# IRIS1304_v2_22.net
KiCad netlist of a schematic drawn in EAGLE
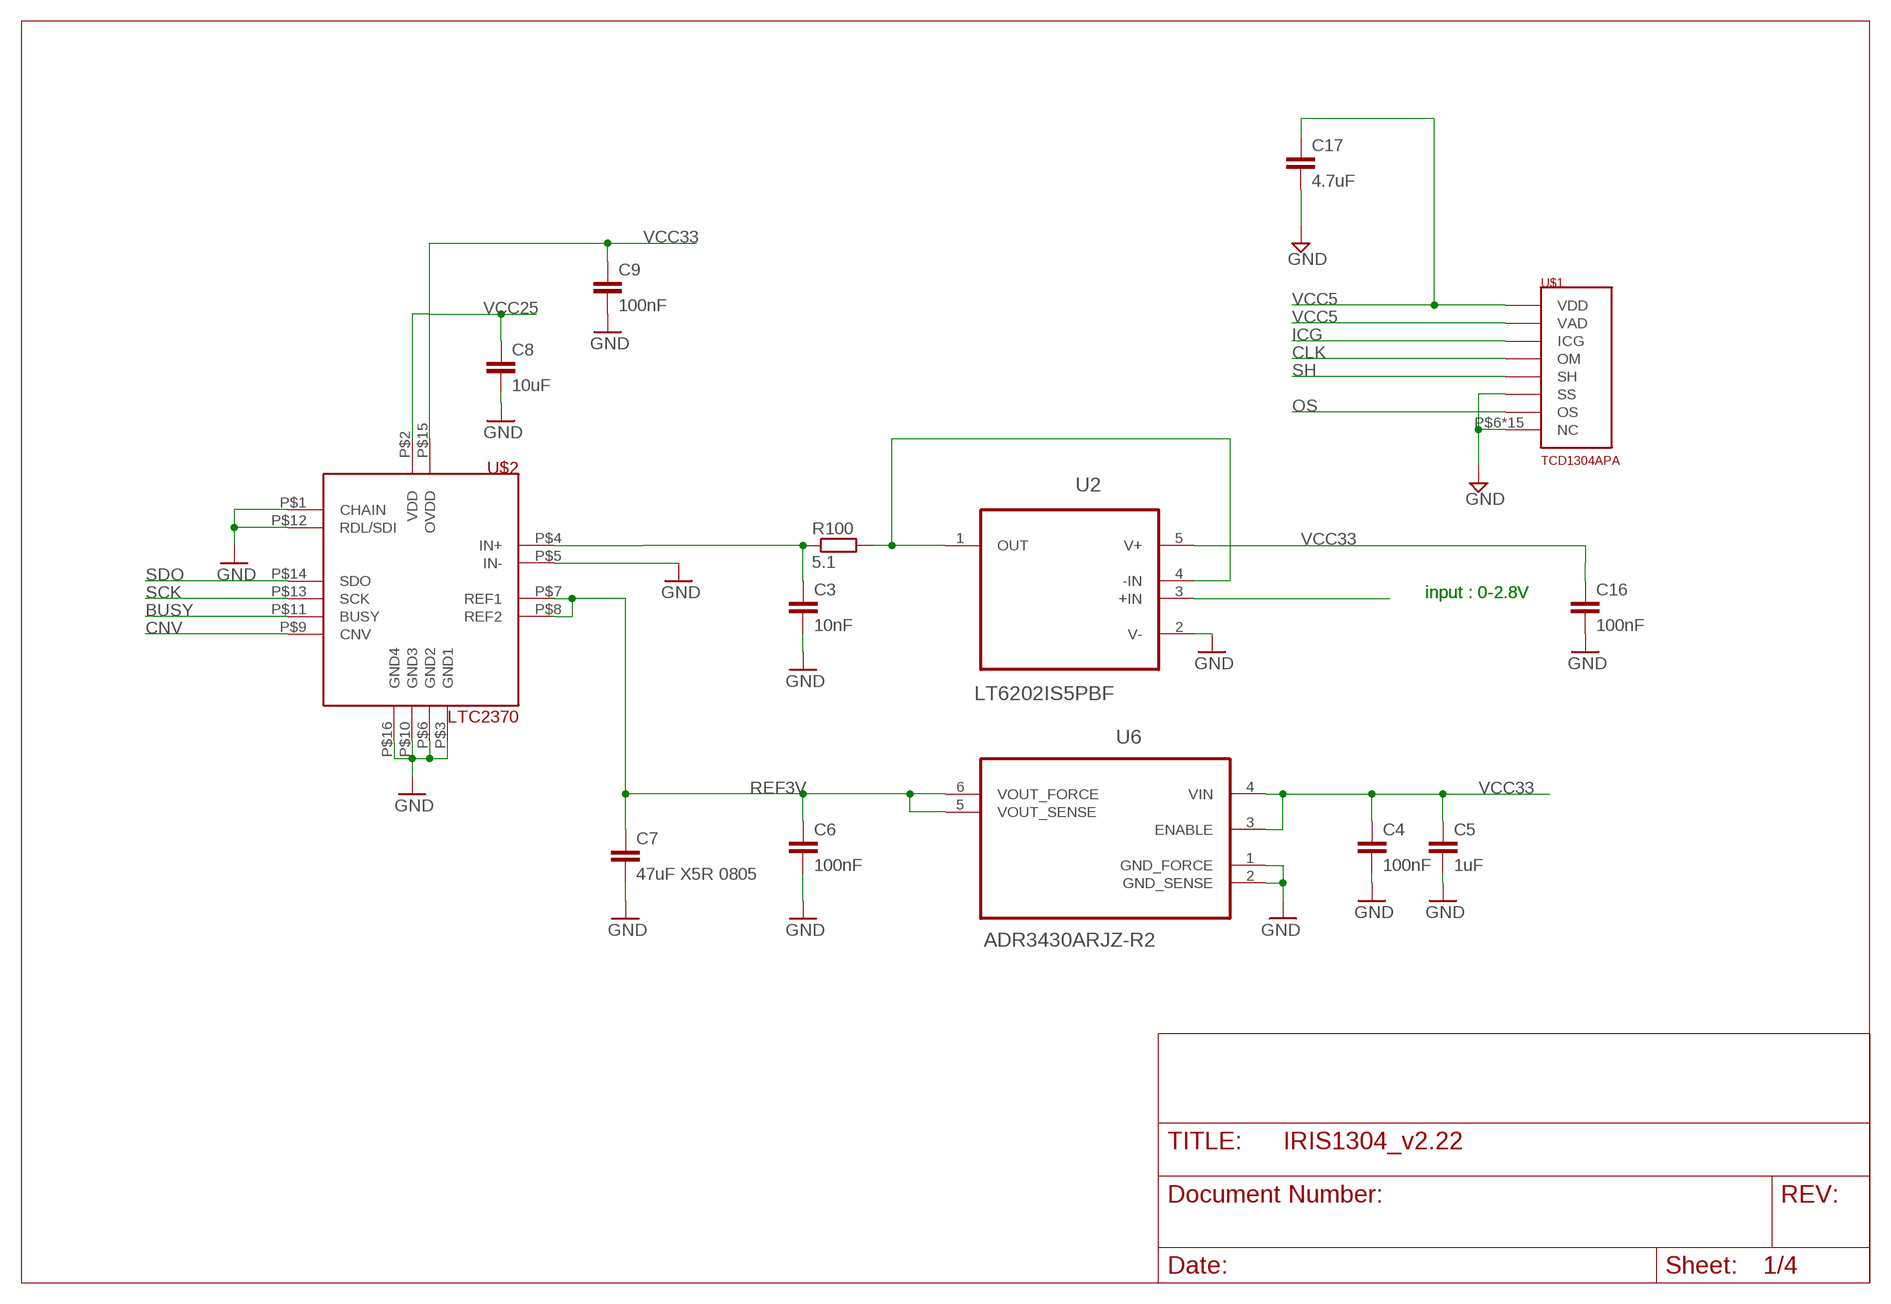
[diagram p0: schematic, sheet 1]
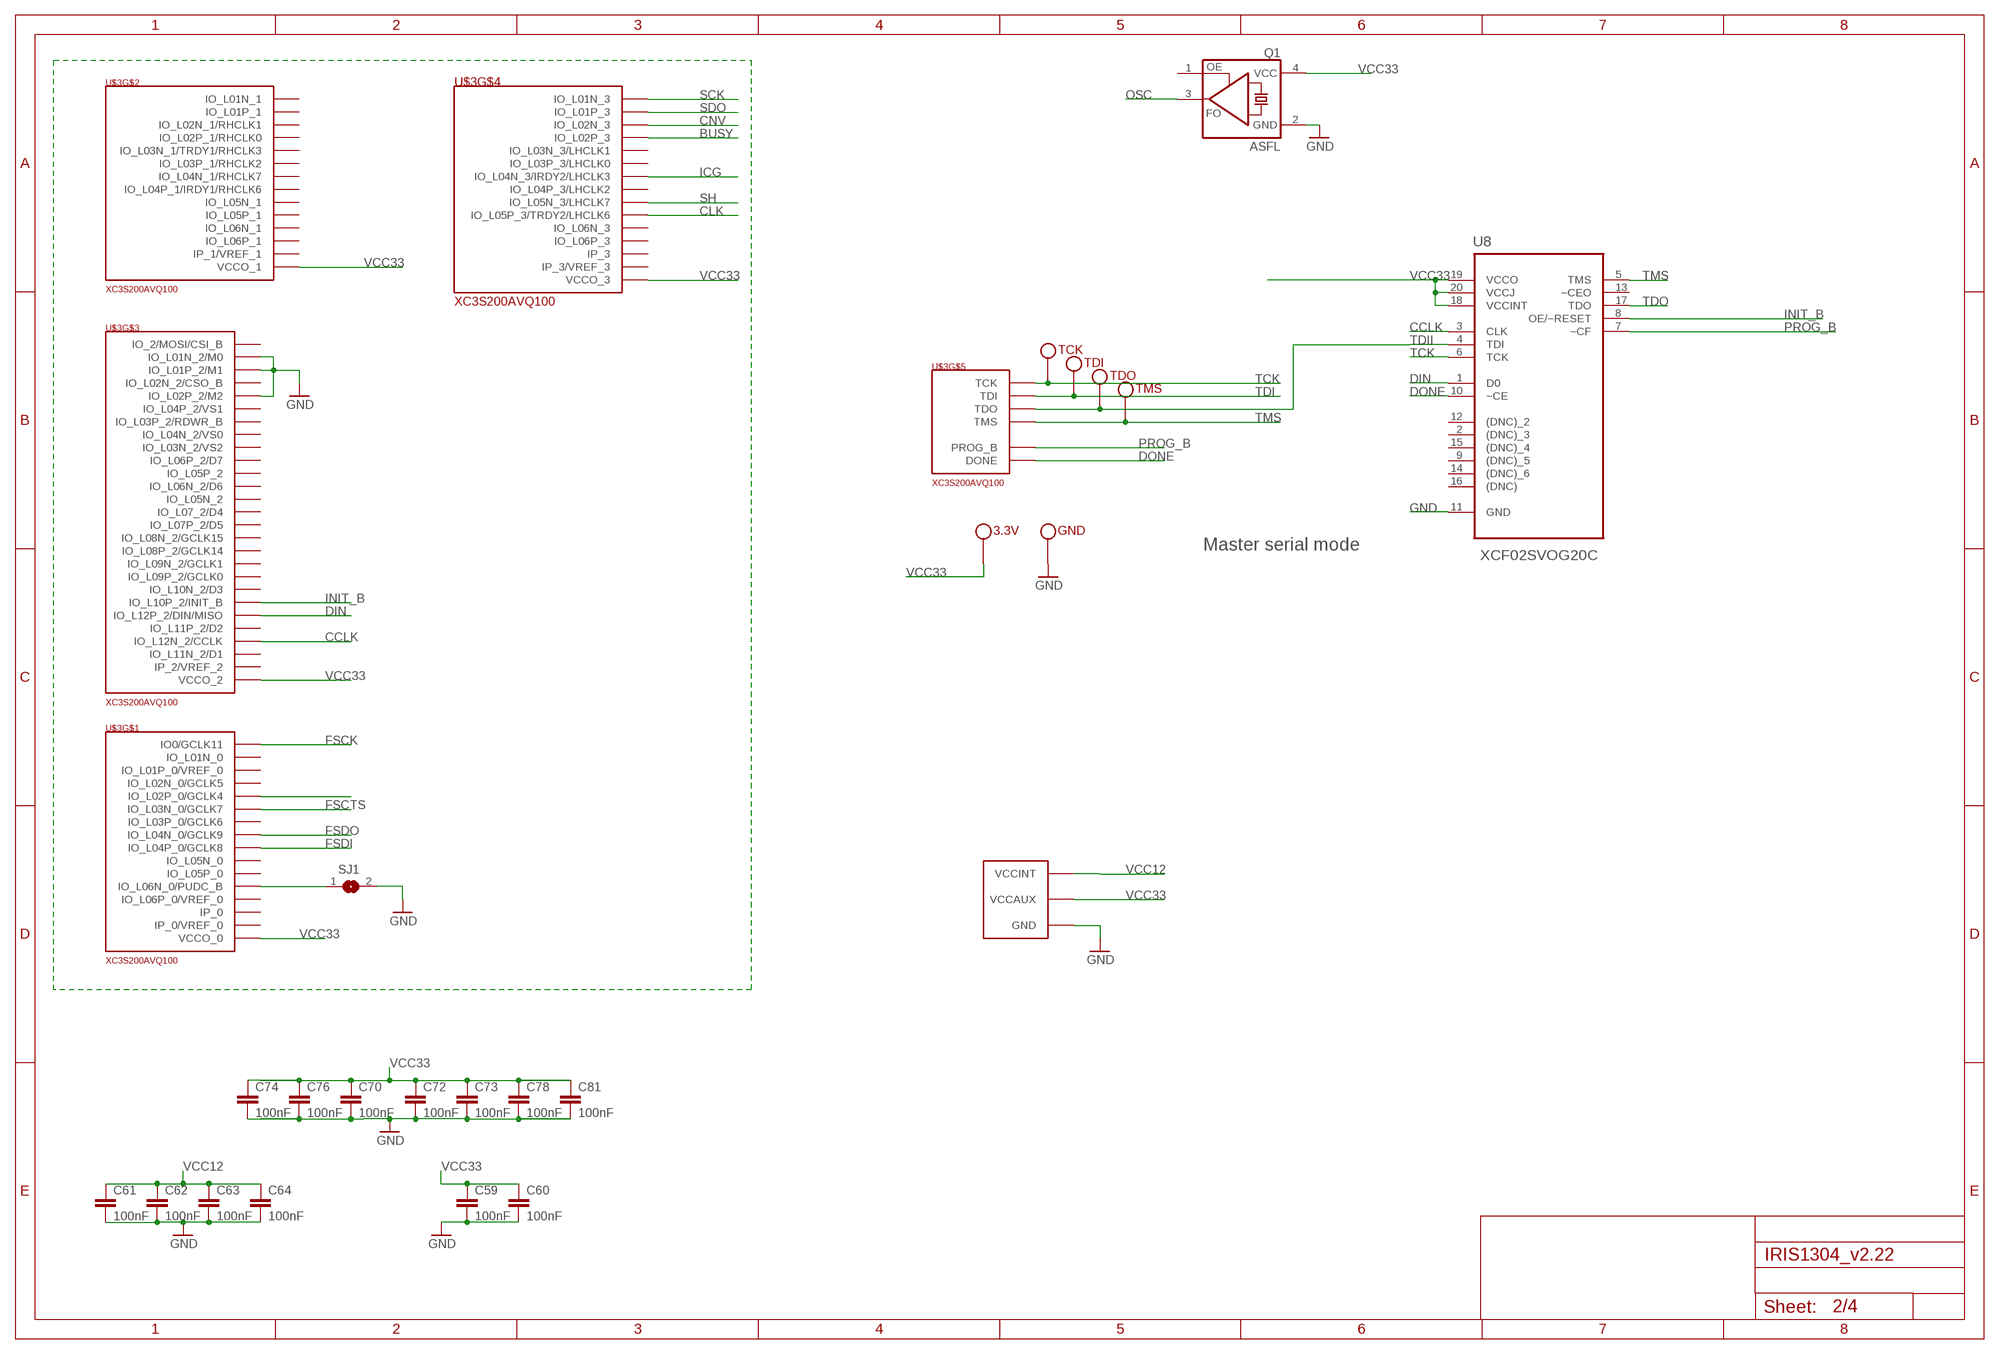
[diagram p1: schematic, sheet 2]
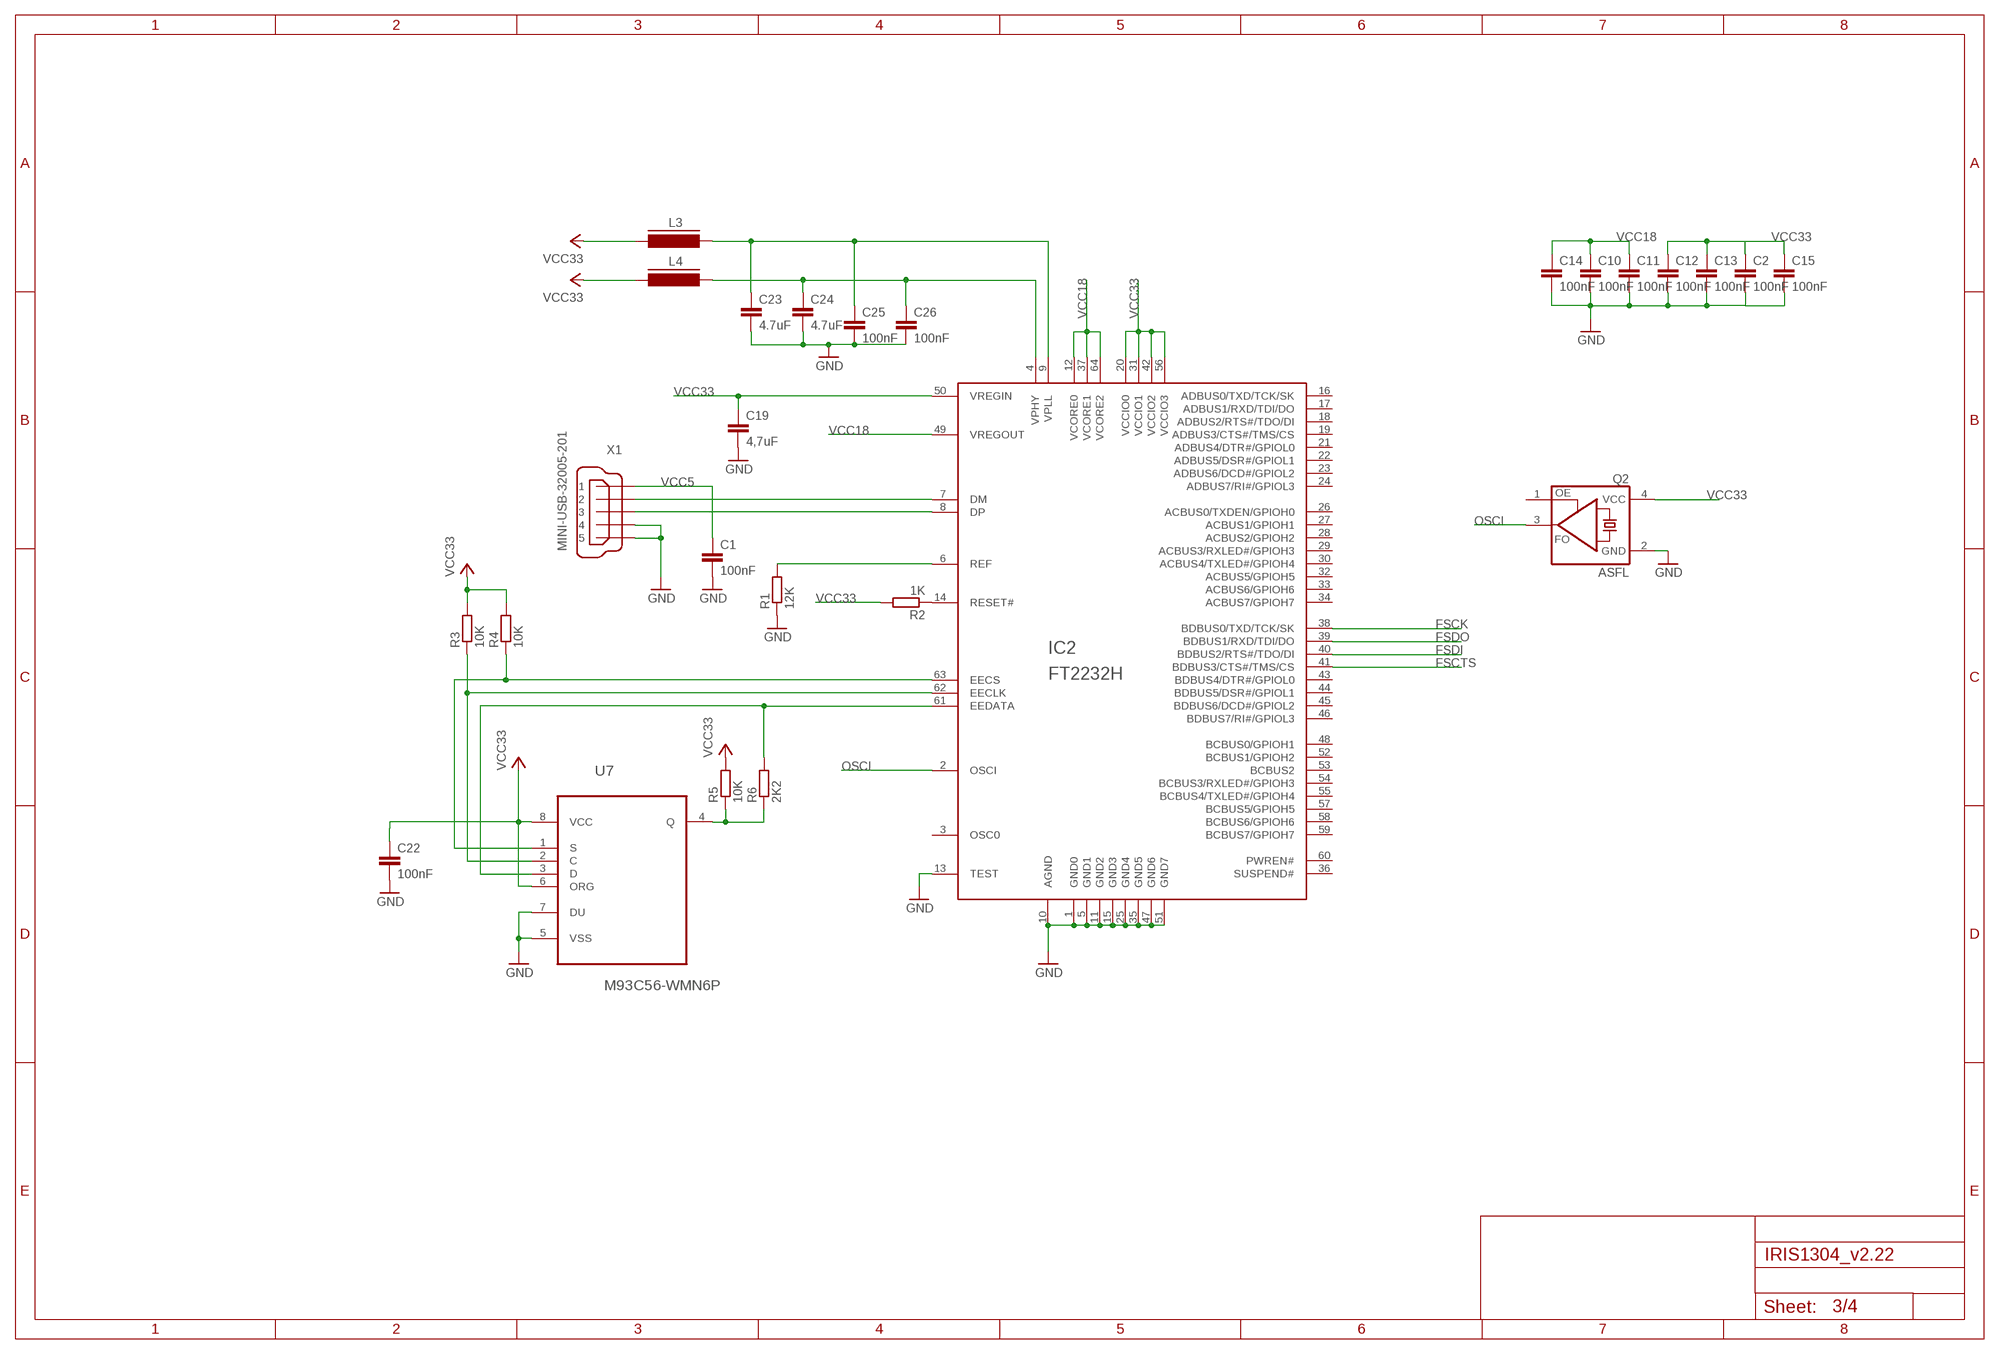
[diagram p2: schematic, sheet 3]
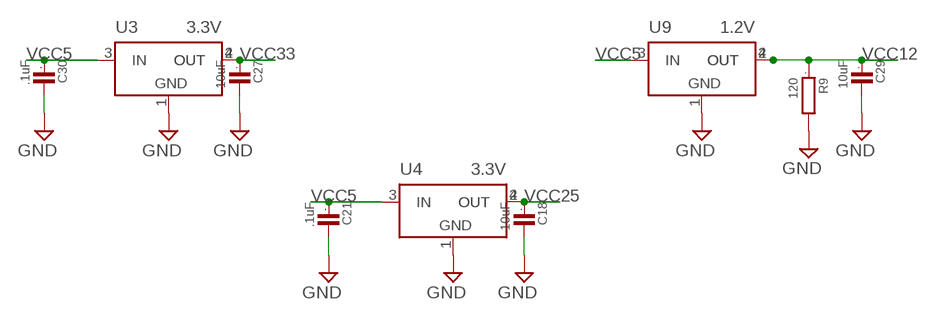
[diagram p3: schematic, sheet 4]

(export (version "E")
  (design (tool "Eeschema 10.0.6"))
  (components
    (comp (ref "C3")
      (value "10nF")
      (footprint "eagle-import:C0603")
      (fields (field (name "MF") "AVX") (field (name "MPN") "06035G103ZAT2A"))
      (libsource (lib "eagle-import") (part "C-EUC0603"))
    )
    (comp (ref "C4")
      (value "100nF")
      (footprint "eagle-import:C0603")
      (fields (field (name "MF") "AVX") (field (name "MPN") "06033G104ZAT2A"))
      (libsource (lib "eagle-import") (part "C-EUC0603"))
    )
    (comp (ref "C5")
      (value "1uF")
      (footprint "eagle-import:C0603")
      (fields (field (name "MF") "KEMET") (field (name "MPN") "C0603C105K3PACTU"))
      (libsource (lib "eagle-import") (part "C-EUC0603"))
    )
    (comp (ref "C6")
      (value "100nF")
      (footprint "eagle-import:C0603")
      (fields (field (name "MF") "AVX") (field (name "MPN") "06033G104ZAT2A"))
      (libsource (lib "eagle-import") (part "C-EUC0603"))
    )
    (comp (ref "C7")
      (value "47uF X5R 0805")
      (footprint "eagle-import:C0805")
      (fields (field (name "MF") "KEMET") (field (name "MPN") "C0805C476M9PACTU"))
      (libsource (lib "eagle-import") (part "C-EUC0805"))
    )
    (comp (ref "C8")
      (value "10uF")
      (footprint "eagle-import:C0603")
      (fields (field (name "MF") "KEMET") (field (name "MPN") "C0603C106M9PACTU"))
      (libsource (lib "eagle-import") (part "C-EUC0603"))
    )
    (comp (ref "C9")
      (value "100nF")
      (footprint "eagle-import:C0603")
      (fields (field (name "MF") "AVX") (field (name "MPN") "06033G104ZAT2A"))
      (libsource (lib "eagle-import") (part "C-EUC0603"))
    )
    (comp (ref "C16")
      (value "100nF")
      (footprint "eagle-import:C0603")
      (fields (field (name "MF") "AVX") (field (name "MPN") "06033G104ZAT2A"))
      (libsource (lib "eagle-import") (part "C-EUC0603"))
    )
    (comp (ref "C17")
      (value "4.7uF")
      (footprint "eagle-import:C0603")
      (fields (field (name "MF") "YAGEO (PHYCOMP)") (field (name "MPN") "CC0603KRX5R6BB475"))
      (libsource (lib "eagle-import") (part "C-EUC0603"))
    )
    (comp (ref "R100")
      (value "5.1")
      (footprint "eagle-import:R0603")
      (fields (field (name "MF") "VISHAY DALE") (field (name "MPN") "CRCW06035R10FNEA"))
      (libsource (lib "eagle-import") (part "R-EU_R0603"))
    )
    (comp (ref "U$1")
      (value "TCD1304APA")
      (footprint "eagle-import:ILX511")
      (libsource (lib "eagle-import") (part "TCD1304APA"))
    )
    (comp (ref "U$2")
      (value "LTC2370")
      (footprint "eagle-import:MSOP-16")
      (fields (field (name "MF") "LINEAR TECHNOLOGY") (field (name "MPN") "LTC2370CMS-16"))
      (libsource (lib "eagle-import") (part "LTC2370"))
    )
    (comp (ref "U2")
      (value "LT6202IS5PBF")
      (footprint "eagle-import:SOT95P280X100-5N")
      (fields (field (name "MPN") "LT6202IS5#PBF") (field (name "MF") "LINEAR TECHNOLOGY"))
      (libsource (lib "eagle-import") (part "LT6202IS5PBF"))
    )
    (comp (ref "U6")
      (value "ADR3430ARJZ-R2")
      (footprint "eagle-import:SOT95P280X145-6N")
      (fields (field (name "MF") "ANALOG DEVICES"))
      (libsource (lib "eagle-import") (part "ADR3430ARJZ-R2"))
    )
    (comp (ref "C1")
      (value "100nF")
      (footprint "eagle-import:C0603")
      (fields (field (name "MF") "AVX") (field (name "MPN") "06035G103ZAT2A"))
      (libsource (lib "eagle-import") (part "C-EUC0603"))
    )
    (comp (ref "C2")
      (value "100nF")
      (footprint "eagle-import:C0603")
      (fields (field (name "MF") "AVX") (field (name "MPN") "06033G104ZAT2A"))
      (libsource (lib "eagle-import") (part "C-EUC0603"))
    )
    (comp (ref "C10")
      (value "100nF")
      (footprint "eagle-import:C0603")
      (fields (field (name "MF") "AVX") (field (name "MPN") "06033G104ZAT2A"))
      (libsource (lib "eagle-import") (part "C-EUC0603"))
    )
    (comp (ref "C11")
      (value "100nF")
      (footprint "eagle-import:C0603")
      (fields (field (name "MF") "AVX") (field (name "MPN") "06033G104ZAT2A"))
      (libsource (lib "eagle-import") (part "C-EUC0603"))
    )
    (comp (ref "C12")
      (value "100nF")
      (footprint "eagle-import:C0603")
      (fields (field (name "MF") "AVX") (field (name "MPN") "06033G104ZAT2A"))
      (libsource (lib "eagle-import") (part "C-EUC0603"))
    )
    (comp (ref "C13")
      (value "100nF")
      (footprint "eagle-import:C0603")
      (fields (field (name "MF") "AVX") (field (name "MPN") "06033G104ZAT2A"))
      (libsource (lib "eagle-import") (part "C-EUC0603"))
    )
    (comp (ref "C14")
      (value "100nF")
      (footprint "eagle-import:C0603")
      (fields (field (name "MF") "AVX") (field (name "MPN") "06033G104ZAT2A"))
      (libsource (lib "eagle-import") (part "C-EUC0603"))
    )
    (comp (ref "C15")
      (value "100nF")
      (footprint "eagle-import:C0603")
      (fields (field (name "MF") "AVX") (field (name "MPN") "06033G104ZAT2A"))
      (libsource (lib "eagle-import") (part "C-EUC0603"))
    )
    (comp (ref "C19")
      (value "4,7uF")
      (footprint "eagle-import:C0805")
      (fields (field (name "MF") "AVX") (field (name "MPN") "0805ZD335KAT2A"))
      (libsource (lib "eagle-import") (part "C-EUC0805"))
    )
    (comp (ref "C22")
      (value "100nF")
      (footprint "eagle-import:C0603")
      (fields (field (name "MF") "AVX") (field (name "MPN") "06033G104ZAT2A"))
      (libsource (lib "eagle-import") (part "C-EUC0603"))
    )
    (comp (ref "C23")
      (value "4.7uF")
      (footprint "eagle-import:C0603")
      (fields (field (name "MF") "YAGEO (PHYCOMP)") (field (name "MPN") "CC0603KRX5R6BB475"))
      (libsource (lib "eagle-import") (part "C-EUC0603"))
    )
    (comp (ref "C24")
      (value "4.7uF")
      (footprint "eagle-import:C0603")
      (fields (field (name "MF") "YAGEO (PHYCOMP)") (field (name "MPN") "CC0603KRX5R6BB475"))
      (libsource (lib "eagle-import") (part "C-EUC0603"))
    )
    (comp (ref "C25")
      (value "100nF")
      (footprint "eagle-import:C0603")
      (fields (field (name "MF") "AVX") (field (name "MPN") "06033G104ZAT2A"))
      (libsource (lib "eagle-import") (part "C-EUC0603"))
    )
    (comp (ref "C26")
      (value "100nF")
      (footprint "eagle-import:C0603")
      (fields (field (name "MF") "AVX") (field (name "MPN") "06033G104ZAT2A"))
      (libsource (lib "eagle-import") (part "C-EUC0603"))
    )
    (comp (ref "IC2")
      (value "FT2232H")
      (footprint "eagle-import:LQFP64")
      (fields (field (name "MF") "FTDI") (field (name "MPN") "FT2232HL-R"))
      (libsource (lib "eagle-import") (part "FT2232H"))
    )
    (comp (ref "L3")
      (value "FERRITE_BEAD805")
      (footprint "eagle-import:FB805")
      (libsource (lib "eagle-import") (part "FERRITE_BEAD805"))
    )
    (comp (ref "L4")
      (value "FERRITE_BEAD805")
      (footprint "eagle-import:FB805")
      (libsource (lib "eagle-import") (part "FERRITE_BEAD805"))
    )
    (comp (ref "Q2")
      (value "ASFL")
      (footprint "eagle-import:ASF")
      (fields
        (field (name "MPN") "ASFLM1-50.000MHZ-C-T")
        (field (name "MF") "ABRACON")
        (field (name "MPN_1") "ASFL1-12.000MHZ-EK-T")
        (field (name "OC_FARNELL") "7943088")
      )
      (libsource (lib "eagle-import") (part "ASFL"))
    )
    (comp (ref "R1")
      (value "12K")
      (footprint "eagle-import:R0603")
      (fields (field (name "MF") "TE CONNECTIVITY") (field (name "MPN") "CPF0201D12K1C1"))
      (libsource (lib "eagle-import") (part "R-EU_R0603"))
    )
    (comp (ref "R2")
      (value "1K")
      (footprint "eagle-import:R0603")
      (fields (field (name "MF") "VISHAY DRALORIC") (field (name "MPN") "CRCW06031K00FKEA"))
      (libsource (lib "eagle-import") (part "R-EU_R0603"))
    )
    (comp (ref "R3")
      (value "10K")
      (footprint "eagle-import:R0603")
      (fields (field (name "MF") "TE CONNECTIVITY / NEOHM") (field (name "MPN") "CPF0603F10KC1"))
      (libsource (lib "eagle-import") (part "R-EU_R0603"))
    )
    (comp (ref "R4")
      (value "10K")
      (footprint "eagle-import:R0603")
      (fields (field (name "MF") "TE CONNECTIVITY / NEOHM") (field (name "MPN") "CPF0603F10KC1"))
      (libsource (lib "eagle-import") (part "R-EU_R0603"))
    )
    (comp (ref "R5")
      (value "10K")
      (footprint "eagle-import:R0603")
      (fields (field (name "MF") "TE CONNECTIVITY / NEOHM") (field (name "MPN") "CPF0603F10KC1"))
      (libsource (lib "eagle-import") (part "R-EU_R0603"))
    )
    (comp (ref "R6")
      (value "2K2")
      (footprint "eagle-import:R0603")
      (fields (field (name "MF") "PANASONIC") (field (name "MPN") "ERJP03F2201V"))
      (libsource (lib "eagle-import") (part "R-EU_R0603"))
    )
    (comp (ref "U7")
      (value "M93C56-WMN6P")
      (footprint "eagle-import:SOIC127P600X175-8N")
      (fields (field (name "MF") "STMICROELECTRONICS"))
      (libsource (lib "eagle-import") (part "M93C56-WMN6P"))
    )
    (comp (ref "X1")
      (value "MINI-USB-32005-201")
      (footprint "eagle-import:32005-201")
      (fields
        (field (name "MF") "WURTH ELEKTRONIK")
        (field (name "MPN") "65100516121")
        (field (name "OC_FARNELL") "1642036")
      )
      (libsource (lib "eagle-import") (part "MINI-USB-32005-201"))
    )
    (comp (ref "C18")
      (value "10uF")
      (footprint "eagle-import:0805")
      (libsource (lib "eagle-import") (part "C0805"))
    )
    (comp (ref "C21")
      (value ".1uF")
      (footprint "eagle-import:0805")
      (libsource (lib "eagle-import") (part "C0805"))
    )
    (comp (ref "C27")
      (value "10uF")
      (footprint "eagle-import:0805")
      (libsource (lib "eagle-import") (part "C0805"))
    )
    (comp (ref "C29")
      (value "10uF")
      (footprint "eagle-import:0805")
      (libsource (lib "eagle-import") (part "C0805"))
    )
    (comp (ref "C30")
      (value ".1uF")
      (footprint "eagle-import:0805")
      (libsource (lib "eagle-import") (part "C0805"))
    )
    (comp (ref "R9")
      (value "120")
      (footprint "eagle-import:0805@1")
      (libsource (lib "eagle-import") (part "R0805"))
    )
    (comp (ref "U3")
      (value "3.3V")
      (footprint "eagle-import:SOT223")
      (libsource (lib "eagle-import") (part "LD1117"))
    )
    (comp (ref "U4")
      (value "3.3V")
      (footprint "eagle-import:SOT223")
      (libsource (lib "eagle-import") (part "LD1117"))
    )
    (comp (ref "U9")
      (value "1.2V")
      (footprint "eagle-import:SOT223")
      (libsource (lib "eagle-import") (part "LD1117"))
    )
    (comp (ref "3.3V")
      (value "TEST")
      (footprint "eagle-import:TEST")
      (libsource (lib "eagle-import") (part "TEST"))
    )
    (comp (ref "C59")
      (value "100nF")
      (footprint "eagle-import:C0603")
      (fields (field (name "MF") "AVX") (field (name "MPN") "06033G104ZAT2A"))
      (libsource (lib "eagle-import") (part "C-EUC0603"))
    )
    (comp (ref "C60")
      (value "100nF")
      (footprint "eagle-import:C0603")
      (fields (field (name "MF") "AVX") (field (name "MPN") "06033G104ZAT2A"))
      (libsource (lib "eagle-import") (part "C-EUC0603"))
    )
    (comp (ref "C61")
      (value "100nF")
      (footprint "eagle-import:C0603")
      (fields (field (name "MF") "AVX") (field (name "MPN") "06033G104ZAT2A"))
      (libsource (lib "eagle-import") (part "C-EUC0603"))
    )
    (comp (ref "C62")
      (value "100nF")
      (footprint "eagle-import:C0603")
      (fields (field (name "MF") "AVX") (field (name "MPN") "06033G104ZAT2A"))
      (libsource (lib "eagle-import") (part "C-EUC0603"))
    )
    (comp (ref "C63")
      (value "100nF")
      (footprint "eagle-import:C0603")
      (fields (field (name "MF") "AVX") (field (name "MPN") "06033G104ZAT2A"))
      (libsource (lib "eagle-import") (part "C-EUC0603"))
    )
    (comp (ref "C64")
      (value "100nF")
      (footprint "eagle-import:C0603")
      (fields (field (name "MF") "AVX") (field (name "MPN") "06033G104ZAT2A"))
      (libsource (lib "eagle-import") (part "C-EUC0603"))
    )
    (comp (ref "C70")
      (value "100nF")
      (footprint "eagle-import:C0603")
      (fields (field (name "MF") "AVX") (field (name "MPN") "06033G104ZAT2A"))
      (libsource (lib "eagle-import") (part "C-EUC0603"))
    )
    (comp (ref "C72")
      (value "100nF")
      (footprint "eagle-import:C0603")
      (fields (field (name "MF") "AVX") (field (name "MPN") "06033G104ZAT2A"))
      (libsource (lib "eagle-import") (part "C-EUC0603"))
    )
    (comp (ref "C73")
      (value "100nF")
      (footprint "eagle-import:C0603")
      (fields (field (name "MF") "AVX") (field (name "MPN") "06033G104ZAT2A"))
      (libsource (lib "eagle-import") (part "C-EUC0603"))
    )
    (comp (ref "C74")
      (value "100nF")
      (footprint "eagle-import:C0603")
      (fields (field (name "MF") "AVX") (field (name "MPN") "06033G104ZAT2A"))
      (libsource (lib "eagle-import") (part "C-EUC0603"))
    )
    (comp (ref "C76")
      (value "100nF")
      (footprint "eagle-import:C0603")
      (fields (field (name "MF") "AVX") (field (name "MPN") "06033G104ZAT2A"))
      (libsource (lib "eagle-import") (part "C-EUC0603"))
    )
    (comp (ref "C78")
      (value "100nF")
      (footprint "eagle-import:C0603")
      (fields (field (name "MF") "AVX") (field (name "MPN") "06033G104ZAT2A"))
      (libsource (lib "eagle-import") (part "C-EUC0603"))
    )
    (comp (ref "C81")
      (value "100nF")
      (footprint "eagle-import:C0603")
      (fields (field (name "MF") "AVX") (field (name "MPN") "06033G104ZAT2A"))
      (libsource (lib "eagle-import") (part "C-EUC0603"))
    )
    (comp (ref "GND")
      (value "TEST")
      (footprint "eagle-import:TEST")
      (libsource (lib "eagle-import") (part "TEST"))
    )
    (comp (ref "Q1")
      (value "ASFL")
      (footprint "eagle-import:ASF")
      (fields
        (field (name "MPN") "ASFLM1-50.000MHZ-C-T")
        (field (name "MF") "ABRACON")
        (field (name "MPN_1") "ASFL1-12.000MHZ-EK-T")
        (field (name "OC_FARNELL") "7943088")
      )
      (libsource (lib "eagle-import") (part "ASFL"))
    )
    (comp (ref "SJ1") (value "SJ") (footprint "eagle-import:SJ") (libsource (lib "eagle-import") (part "SJ")))
    (comp (ref "TCK")
      (value "TEST")
      (footprint "eagle-import:TEST")
      (libsource (lib "eagle-import") (part "TEST"))
    )
    (comp (ref "TDI")
      (value "TEST")
      (footprint "eagle-import:TEST")
      (libsource (lib "eagle-import") (part "TEST"))
    )
    (comp (ref "TDO")
      (value "TEST")
      (footprint "eagle-import:TEST")
      (libsource (lib "eagle-import") (part "TEST"))
    )
    (comp (ref "TMS")
      (value "TEST")
      (footprint "eagle-import:TEST")
      (libsource (lib "eagle-import") (part "TEST"))
    )
    (comp (ref "U$3")
      (value "XC3S200AVQ100")
      (footprint "eagle-import:VQ100")
      (libsource (lib "eagle-import") (part "XC3S200AVQ100"))
    )
    (comp (ref "U8")
      (value "XCF02SVOG20C")
      (footprint "eagle-import:SOP65P640X119-20N")
      (fields (field (name "MF") "XILINX"))
      (libsource (lib "eagle-import") (part "XCF02SVOG20C"))
    )
  )
  (nets
    (net (code "1") (name "BUSY") (class "Default")
      (node (ref "U$2") (pin "P$11") (pinfunction "BUSY_P$11") (pintype "bidirectional"))
      (node (ref "U$3") (pin "P5") (pinfunction "IO_L02P_3_P5") (pintype "bidirectional"))
    )
    (net (code "2") (name "CCLK") (class "Default")
      (node (ref "U$3") (pin "P53") (pinfunction "IO_L12N_2/CCLK_P53") (pintype "bidirectional"))
      (node (ref "U8") (pin "3") (pinfunction "CLK_3") (pintype "input"))
    )
    (net (code "3") (name "CLK") (class "Default")
      (node (ref "U$1") (pin "P$4") (pinfunction "OM_P$4") (pintype "bidirectional"))
      (node (ref "U$3") (pin "P15") (pinfunction "IO_L05P_3/TRDY2/LHCLK6_P15") (pintype "bidirectional"))
    )
    (net (code "4") (name "CNV") (class "Default")
      (node (ref "U$2") (pin "P$9") (pinfunction "CNV_P$9") (pintype "bidirectional"))
      (node (ref "U$3") (pin "P6") (pinfunction "IO_L02N_3_P6") (pintype "bidirectional"))
    )
    (net (code "5") (name "DIN") (class "Default")
      (node (ref "U$3") (pin "P51") (pinfunction "IO_L12P_2/DIN/MISO_P51") (pintype "bidirectional"))
      (node (ref "U8") (pin "1") (pinfunction "D0_1") (pintype "input"))
    )
    (net (code "6") (name "DONE") (class "Default")
      (node (ref "U$3") (pin "P54") (pinfunction "DONE_P54") (pintype "bidirectional"))
      (node (ref "U8") (pin "10") (pinfunction "~{CE}_10") (pintype "input"))
    )
    (net (code "7") (name "FSCK") (class "Default")
      (node (ref "IC2") (pin "38") (pinfunction "BDBUS0/TXD/TCK/SK_38") (pintype "bidirectional"))
      (node (ref "U$3") (pin "P90") (pinfunction "IO0/GCLK11_P90") (pintype "bidirectional"))
    )
    (net (code "8") (name "FSCTS") (class "Default")
      (node (ref "IC2") (pin "41") (pinfunction "BDBUS3/CTS#/TMS/CS_41") (pintype "bidirectional"))
      (node (ref "U$3") (pin "P86") (pinfunction "IO_L03N_0/GCLK7_P86") (pintype "bidirectional"))
    )
    (net (code "9") (name "FSDI") (class "Default")
      (node (ref "IC2") (pin "40") (pinfunction "BDBUS2/RTS#/TDO/DI_40") (pintype "bidirectional"))
      (node (ref "U$3") (pin "P88") (pinfunction "IO_L04P_0/GCLK8_P88") (pintype "bidirectional"))
    )
    (net (code "10") (name "FSDO") (class "Default")
      (node (ref "IC2") (pin "39") (pinfunction "BDBUS1/RXD/TDI/DO_39") (pintype "bidirectional"))
      (node (ref "U$3") (pin "P89") (pinfunction "IO_L04N_0/GCLK9_P89") (pintype "bidirectional"))
    )
    (net (code "11") (name "GND") (class "Default")
      (node (ref "C1") (pin "2") (pinfunction "2_2") (pintype "passive"))
      (node (ref "C10") (pin "2") (pinfunction "2_2") (pintype "passive"))
      (node (ref "C11") (pin "2") (pinfunction "2_2") (pintype "passive"))
      (node (ref "C12") (pin "2") (pinfunction "2_2") (pintype "passive"))
      (node (ref "C13") (pin "2") (pinfunction "2_2") (pintype "passive"))
      (node (ref "C14") (pin "2") (pinfunction "2_2") (pintype "passive"))
      (node (ref "C15") (pin "2") (pinfunction "2_2") (pintype "passive"))
      (node (ref "C16") (pin "2") (pinfunction "2_2") (pintype "passive"))
      (node (ref "C17") (pin "2") (pinfunction "2_2") (pintype "passive"))
      (node (ref "C18") (pin "2") (pinfunction "2_2") (pintype "passive"))
      (node (ref "C19") (pin "2") (pinfunction "2_2") (pintype "passive"))
      (node (ref "C2") (pin "2") (pinfunction "2_2") (pintype "passive"))
      (node (ref "C21") (pin "2") (pinfunction "2_2") (pintype "passive"))
      (node (ref "C22") (pin "2") (pinfunction "2_2") (pintype "passive"))
      (node (ref "C23") (pin "2") (pinfunction "2_2") (pintype "passive"))
      (node (ref "C24") (pin "2") (pinfunction "2_2") (pintype "passive"))
      (node (ref "C25") (pin "2") (pinfunction "2_2") (pintype "passive"))
      (node (ref "C26") (pin "2") (pinfunction "2_2") (pintype "passive"))
      (node (ref "C27") (pin "2") (pinfunction "2_2") (pintype "passive"))
      (node (ref "C29") (pin "2") (pinfunction "2_2") (pintype "passive"))
      (node (ref "C3") (pin "2") (pinfunction "2_2") (pintype "passive"))
      (node (ref "C30") (pin "2") (pinfunction "2_2") (pintype "passive"))
      (node (ref "C4") (pin "2") (pinfunction "2_2") (pintype "passive"))
      (node (ref "C5") (pin "2") (pinfunction "2_2") (pintype "passive"))
      (node (ref "C59") (pin "2") (pinfunction "2_2") (pintype "passive"))
      (node (ref "C6") (pin "2") (pinfunction "2_2") (pintype "passive"))
      (node (ref "C60") (pin "2") (pinfunction "2_2") (pintype "passive"))
      (node (ref "C61") (pin "2") (pinfunction "2_2") (pintype "passive"))
      (node (ref "C62") (pin "2") (pinfunction "2_2") (pintype "passive"))
      (node (ref "C63") (pin "2") (pinfunction "2_2") (pintype "passive"))
      (node (ref "C64") (pin "2") (pinfunction "2_2") (pintype "passive"))
      (node (ref "C7") (pin "2") (pinfunction "2_2") (pintype "passive"))
      (node (ref "C70") (pin "2") (pinfunction "2_2") (pintype "passive"))
      (node (ref "C72") (pin "2") (pinfunction "2_2") (pintype "passive"))
      (node (ref "C73") (pin "2") (pinfunction "2_2") (pintype "passive"))
      (node (ref "C74") (pin "2") (pinfunction "2_2") (pintype "passive"))
      (node (ref "C76") (pin "2") (pinfunction "2_2") (pintype "passive"))
      (node (ref "C78") (pin "2") (pinfunction "2_2") (pintype "passive"))
      (node (ref "C8") (pin "2") (pinfunction "2_2") (pintype "passive"))
      (node (ref "C81") (pin "2") (pinfunction "2_2") (pintype "passive"))
      (node (ref "C9") (pin "2") (pinfunction "2_2") (pintype "passive"))
      (node (ref "GND") (pin "P$1") (pinfunction "P$1_P$1") (pintype "bidirectional"))
      (node (ref "IC2") (pin "1") (pinfunction "GND0_1") (pintype "bidirectional"))
      (node (ref "IC2") (pin "10") (pinfunction "AGND_10") (pintype "bidirectional"))
      (node (ref "IC2") (pin "11") (pinfunction "GND2_11") (pintype "bidirectional"))
      (node (ref "IC2") (pin "13") (pinfunction "TEST_13") (pintype "bidirectional"))
      (node (ref "IC2") (pin "15") (pinfunction "GND3_15") (pintype "bidirectional"))
      (node (ref "IC2") (pin "25") (pinfunction "GND4_25") (pintype "bidirectional"))
      (node (ref "IC2") (pin "35") (pinfunction "GND5_35") (pintype "bidirectional"))
      (node (ref "IC2") (pin "47") (pinfunction "GND6_47") (pintype "bidirectional"))
      (node (ref "IC2") (pin "5") (pinfunction "GND1_5") (pintype "bidirectional"))
      (node (ref "IC2") (pin "51") (pinfunction "GND7_51") (pintype "bidirectional"))
      (node (ref "Q1") (pin "2") (pinfunction "GND_2") (pintype "power_in"))
      (node (ref "Q2") (pin "2") (pinfunction "GND_2") (pintype "power_in"))
      (node (ref "R1") (pin "1") (pinfunction "1_1") (pintype "passive"))
      (node (ref "R9") (pin "2") (pinfunction "2_2") (pintype "passive"))
      (node (ref "SJ1") (pin "2") (pinfunction "2_2") (pintype "passive"))
      (node (ref "U$1") (pin "P$10") (pinfunction "NC_P$10") (pintype "bidirectional"))
      (node (ref "U$1") (pin "P$11") (pinfunction "NC_P$11") (pintype "bidirectional"))
      (node (ref "U$1") (pin "P$12") (pinfunction "NC_P$12") (pintype "bidirectional"))
      (node (ref "U$1") (pin "P$13") (pinfunction "NC_P$13") (pintype "bidirectional"))
      (node (ref "U$1") (pin "P$14") (pinfunction "NC_P$14") (pintype "bidirectional"))
      (node (ref "U$1") (pin "P$15") (pinfunction "NC_P$15") (pintype "bidirectional"))
      (node (ref "U$1") (pin "P$16") (pinfunction "NC_P$16") (pintype "bidirectional"))
      (node (ref "U$1") (pin "P$17") (pinfunction "NC_P$17") (pintype "bidirectional"))
      (node (ref "U$1") (pin "P$18") (pinfunction "NC_P$18") (pintype "bidirectional"))
      (node (ref "U$1") (pin "P$19") (pinfunction "NC_P$19") (pintype "bidirectional"))
      (node (ref "U$1") (pin "P$20") (pinfunction "NC_P$20") (pintype "bidirectional"))
      (node (ref "U$1") (pin "P$22") (pinfunction "SS_P$22") (pintype "bidirectional"))
      (node (ref "U$1") (pin "P$6") (pinfunction "NC_P$6") (pintype "bidirectional"))
      (node (ref "U$1") (pin "P$7") (pinfunction "NC_P$7") (pintype "bidirectional"))
      (node (ref "U$1") (pin "P$8") (pinfunction "NC_P$8") (pintype "bidirectional"))
      (node (ref "U$1") (pin "P$9") (pinfunction "NC_P$9") (pintype "bidirectional"))
      (node (ref "U$2") (pin "P$1") (pinfunction "CHAIN_P$1") (pintype "bidirectional"))
      (node (ref "U$2") (pin "P$10") (pinfunction "GND3_P$10") (pintype "bidirectional"))
      (node (ref "U$2") (pin "P$12") (pinfunction "RDL/SDI_P$12") (pintype "bidirectional"))
      (node (ref "U$2") (pin "P$16") (pinfunction "GND4_P$16") (pintype "bidirectional"))
      (node (ref "U$2") (pin "P$3") (pinfunction "GND1_P$3") (pintype "bidirectional"))
      (node (ref "U$2") (pin "P$5") (pinfunction "IN-_P$5") (pintype "bidirectional"))
      (node (ref "U$2") (pin "P$6") (pinfunction "GND2_P$6") (pintype "bidirectional"))
      (node (ref "U$3") (pin "P14") (pinfunction "GND_P14") (pintype "bidirectional"))
      (node (ref "U$3") (pin "P18") (pinfunction "GND_P18") (pintype "bidirectional"))
      (node (ref "U$3") (pin "P23") (pinfunction "IO_L01P_2/M1_P23") (pintype "bidirectional"))
      (node (ref "U$3") (pin "P24") (pinfunction "IO_L02P_2/M2_P24") (pintype "bidirectional"))
      (node (ref "U$3") (pin "P25") (pinfunction "IO_L01N_2/M0_P25") (pintype "bidirectional"))
      (node (ref "U$3") (pin "P42") (pinfunction "GND_P42") (pintype "bidirectional"))
      (node (ref "U$3") (pin "P47") (pinfunction "GND_P47") (pintype "bidirectional"))
      (node (ref "U$3") (pin "P58") (pinfunction "GND_P58") (pintype "bidirectional"))
      (node (ref "U$3") (pin "P63") (pinfunction "GND_P63") (pintype "bidirectional"))
      (node (ref "U$3") (pin "P69") (pinfunction "GND_P69") (pintype "bidirectional"))
      (node (ref "U$3") (pin "P74") (pinfunction "GND_P74") (pintype "bidirectional"))
      (node (ref "U$3") (pin "P8") (pinfunction "GND_P8") (pintype "bidirectional"))
      (node (ref "U$3") (pin "P80") (pinfunction "GND_P80") (pintype "bidirectional"))
      (node (ref "U$3") (pin "P87") (pinfunction "GND_P87") (pintype "bidirectional"))
      (node (ref "U$3") (pin "P91") (pinfunction "GND_P91") (pintype "bidirectional"))
      (node (ref "U$3") (pin "P95") (pinfunction "GND_P95") (pintype "bidirectional"))
      (node (ref "U2") (pin "2") (pinfunction "V-_2") (pintype "power_in"))
      (node (ref "U3") (pin "1") (pinfunction "GND_1") (pintype "power_in"))
      (node (ref "U4") (pin "1") (pinfunction "GND_1") (pintype "power_in"))
      (node (ref "U6") (pin "1") (pinfunction "GND_FORCE_1") (pintype "passive"))
      (node (ref "U6") (pin "2") (pinfunction "GND_SENSE_2") (pintype "passive"))
      (node (ref "U7") (pin "5") (pinfunction "VSS_5") (pintype "power_in"))
      (node (ref "U7") (pin "7") (pinfunction "DU_7") (pintype "input"))
      (node (ref "U8") (pin "11") (pinfunction "GND_11") (pintype "passive"))
      (node (ref "U9") (pin "1") (pinfunction "GND_1") (pintype "power_in"))
      (node (ref "X1") (pin "4") (pinfunction "4_4") (pintype "passive"))
      (node (ref "X1") (pin "5") (pinfunction "5_5") (pintype "passive"))
    )
    (net (code "12") (name "ICG") (class "Default")
      (node (ref "U$1") (pin "P$3") (pinfunction "ICG_P$3") (pintype "bidirectional"))
      (node (ref "U$3") (pin "P13") (pinfunction "IO_L04N_3/IRDY2/LHCLK3_P13") (pintype "bidirectional"))
    )
    (net (code "13") (name "INIT_B") (class "Default")
      (node (ref "U$3") (pin "P48") (pinfunction "IO_L10P_2/INIT_B_P48") (pintype "bidirectional"))
      (node (ref "U8") (pin "8") (pinfunction "OE/~{RESET}_8") (pintype "bidirectional"))
    )
    (net (code "14") (name "Net-(IC2-DM)") (class "Default")
      (node (ref "IC2") (pin "7") (pinfunction "DM_7") (pintype "bidirectional"))
      (node (ref "X1") (pin "2") (pinfunction "2_2") (pintype "passive"))
    )
    (net (code "15") (name "Net-(IC2-DP)") (class "Default")
      (node (ref "IC2") (pin "8") (pinfunction "DP_8") (pintype "bidirectional"))
      (node (ref "X1") (pin "3") (pinfunction "3_3") (pintype "passive"))
    )
    (net (code "16") (name "Net-(IC2-EECLK)") (class "Default")
      (node (ref "IC2") (pin "62") (pinfunction "EECLK_62") (pintype "bidirectional"))
      (node (ref "R3") (pin "1") (pinfunction "1_1") (pintype "passive"))
      (node (ref "U7") (pin "2") (pinfunction "C_2") (pintype "input"))
    )
    (net (code "17") (name "Net-(IC2-EECS)") (class "Default")
      (node (ref "IC2") (pin "63") (pinfunction "EECS_63") (pintype "bidirectional"))
      (node (ref "R4") (pin "1") (pinfunction "1_1") (pintype "passive"))
      (node (ref "U7") (pin "1") (pinfunction "S_1") (pintype "input"))
    )
    (net (code "18") (name "Net-(IC2-EEDATA)") (class "Default")
      (node (ref "IC2") (pin "61") (pinfunction "EEDATA_61") (pintype "bidirectional"))
      (node (ref "R6") (pin "2") (pinfunction "2_2") (pintype "passive"))
      (node (ref "U7") (pin "3") (pinfunction "D_3") (pintype "input"))
    )
    (net (code "19") (name "Net-(IC2-REF)") (class "Default")
      (node (ref "IC2") (pin "6") (pinfunction "REF_6") (pintype "bidirectional"))
      (node (ref "R1") (pin "2") (pinfunction "2_2") (pintype "passive"))
    )
    (net (code "20") (name "Net-(IC2-RESET#)") (class "Default")
      (node (ref "IC2") (pin "14") (pinfunction "RESET#_14") (pintype "bidirectional"))
      (node (ref "R2") (pin "1") (pinfunction "1_1") (pintype "passive"))
    )
    (net (code "21") (name "Net-(IC2-VPHY)") (class "Default")
      (node (ref "C24") (pin "1") (pinfunction "1_1") (pintype "passive"))
      (node (ref "C26") (pin "1") (pinfunction "1_1") (pintype "passive"))
      (node (ref "IC2") (pin "4") (pinfunction "VPHY_4") (pintype "bidirectional"))
      (node (ref "L4") (pin "1") (pinfunction "1_1") (pintype "passive"))
    )
    (net (code "22") (name "Net-(IC2-VPLL)") (class "Default")
      (node (ref "C23") (pin "1") (pinfunction "1_1") (pintype "passive"))
      (node (ref "C25") (pin "1") (pinfunction "1_1") (pintype "passive"))
      (node (ref "IC2") (pin "9") (pinfunction "VPLL_9") (pintype "bidirectional"))
      (node (ref "L3") (pin "1") (pinfunction "1_1") (pintype "passive"))
    )
    (net (code "23") (name "Net-(U$2-IN+)") (class "Default")
      (node (ref "C3") (pin "1") (pinfunction "1_1") (pintype "passive"))
      (node (ref "R100") (pin "1") (pinfunction "1_1") (pintype "passive"))
      (node (ref "U$2") (pin "P$4") (pinfunction "IN+_P$4") (pintype "bidirectional"))
    )
    (net (code "24") (name "Net-(U$3A-IO_L06N_0{slash}PUDC_B)") (class "Default")
      (node (ref "SJ1") (pin "1") (pinfunction "1_1") (pintype "passive"))
      (node (ref "U$3") (pin "P99") (pinfunction "IO_L06N_0/PUDC_B_P99") (pintype "bidirectional"))
    )
    (net (code "25") (name "Net-(U2--IN)") (class "Default")
      (node (ref "R100") (pin "2") (pinfunction "2_2") (pintype "passive"))
      (node (ref "U2") (pin "1") (pinfunction "OUT_1") (pintype "output"))
      (node (ref "U2") (pin "4") (pinfunction "-IN_4") (pintype "input"))
    )
    (net (code "26") (name "Net-(U7-Q)") (class "Default")
      (node (ref "R5") (pin "1") (pinfunction "1_1") (pintype "passive"))
      (node (ref "R6") (pin "1") (pinfunction "1_1") (pintype "passive"))
      (node (ref "U7") (pin "4") (pinfunction "Q_4") (pintype "output"))
    )
    (net (code "27") (name "OS") (class "Default")
      (node (ref "U$1") (pin "P$21") (pinfunction "OS_P$21") (pintype "bidirectional"))
      (node (ref "U2") (pin "3") (pinfunction "+IN_3") (pintype "input"))
    )
    (net (code "28") (name "OSC") (class "Default")
      (node (ref "Q1") (pin "3") (pinfunction "FO_3") (pintype "output"))
      (node (ref "U$3") (pin "P83") (pinfunction "IO_L02P_0/GCLK4_P83") (pintype "bidirectional"))
    )
    (net (code "29") (name "OSCI") (class "Default")
      (node (ref "IC2") (pin "2") (pinfunction "OSCI_2") (pintype "bidirectional"))
      (node (ref "Q2") (pin "3") (pinfunction "FO_3") (pintype "output"))
    )
    (net (code "30") (name "PROG_B") (class "Default")
      (node (ref "U$3") (pin "P100") (pinfunction "PROG_B_P100") (pintype "bidirectional"))
      (node (ref "U8") (pin "7") (pinfunction "~{CF}_7") (pintype "bidirectional"))
    )
    (net (code "31") (name "REF3V") (class "Default")
      (node (ref "C6") (pin "1") (pinfunction "1_1") (pintype "passive"))
      (node (ref "C7") (pin "1") (pinfunction "1_1") (pintype "passive"))
      (node (ref "U$2") (pin "P$7") (pinfunction "REF1_P$7") (pintype "bidirectional"))
      (node (ref "U$2") (pin "P$8") (pinfunction "REF2_P$8") (pintype "bidirectional"))
      (node (ref "U6") (pin "5") (pinfunction "VOUT_SENSE_5") (pintype "output"))
      (node (ref "U6") (pin "6") (pinfunction "VOUT_FORCE_6") (pintype "output"))
    )
    (net (code "32") (name "SCK") (class "Default")
      (node (ref "U$2") (pin "P$13") (pinfunction "SCK_P$13") (pintype "bidirectional"))
      (node (ref "U$3") (pin "P4") (pinfunction "IO_L01N_3_P4") (pintype "bidirectional"))
    )
    (net (code "33") (name "SDO") (class "Default")
      (node (ref "U$2") (pin "P$14") (pinfunction "SDO_P$14") (pintype "bidirectional"))
      (node (ref "U$3") (pin "P3") (pinfunction "IO_L01P_3_P3") (pintype "bidirectional"))
    )
    (net (code "34") (name "SH") (class "Default")
      (node (ref "U$1") (pin "P$5") (pinfunction "SH_P$5") (pintype "bidirectional"))
      (node (ref "U$3") (pin "P16") (pinfunction "IO_L05N_3/LHCLK7_P16") (pintype "bidirectional"))
    )
    (net (code "35") (name "TCK") (class "Default")
      (node (ref "TCK") (pin "P$1") (pinfunction "P$1_P$1") (pintype "bidirectional"))
      (node (ref "U$3") (pin "P76") (pinfunction "TCK_P76") (pintype "bidirectional"))
      (node (ref "U8") (pin "6") (pinfunction "TCK_6") (pintype "input"))
    )
    (net (code "36") (name "TDI") (class "Default")
      (node (ref "TDI") (pin "P$1") (pinfunction "P$1_P$1") (pintype "bidirectional"))
      (node (ref "U$3") (pin "P2") (pinfunction "TDI_P2") (pintype "bidirectional"))
    )
    (net (code "37") (name "TDII") (class "Default")
      (node (ref "TDO") (pin "P$1") (pinfunction "P$1_P$1") (pintype "bidirectional"))
      (node (ref "U$3") (pin "P75") (pinfunction "TDO_P75") (pintype "bidirectional"))
      (node (ref "U8") (pin "4") (pinfunction "TDI_4") (pintype "input"))
    )
    (net (code "38") (name "TDO") (class "Default")
      (node (ref "U8") (pin "17") (pinfunction "TDO_17") (pintype "output"))
    )
    (net (code "39") (name "TMS") (class "Default")
      (node (ref "TMS") (pin "P$1") (pinfunction "P$1_P$1") (pintype "bidirectional"))
      (node (ref "U$3") (pin "P1") (pinfunction "TMS_P1") (pintype "bidirectional"))
      (node (ref "U8") (pin "5") (pinfunction "TMS_5") (pintype "input"))
    )
    (net (code "40") (name "VCC5") (class "Default")
      (node (ref "C1") (pin "1") (pinfunction "1_1") (pintype "passive"))
      (node (ref "C17") (pin "1") (pinfunction "1_1") (pintype "passive"))
      (node (ref "C21") (pin "1") (pinfunction "1_1") (pintype "passive"))
      (node (ref "C30") (pin "1") (pinfunction "1_1") (pintype "passive"))
      (node (ref "U$1") (pin "P$1") (pinfunction "VDD_P$1") (pintype "bidirectional"))
      (node (ref "U$1") (pin "P$2") (pinfunction "VAD_P$2") (pintype "bidirectional"))
      (node (ref "U3") (pin "3") (pinfunction "IN_3") (pintype "input"))
      (node (ref "U4") (pin "3") (pinfunction "IN_3") (pintype "input"))
      (node (ref "U9") (pin "3") (pinfunction "IN_3") (pintype "input"))
      (node (ref "X1") (pin "1") (pinfunction "1_1") (pintype "passive"))
    )
    (net (code "41") (name "VCC12") (class "Default")
      (node (ref "C29") (pin "1") (pinfunction "1_1") (pintype "passive"))
      (node (ref "C61") (pin "1") (pinfunction "1_1") (pintype "passive"))
      (node (ref "C62") (pin "1") (pinfunction "1_1") (pintype "passive"))
      (node (ref "C63") (pin "1") (pinfunction "1_1") (pintype "passive"))
      (node (ref "C64") (pin "1") (pinfunction "1_1") (pintype "passive"))
      (node (ref "R9") (pin "1") (pinfunction "1_1") (pintype "passive"))
      (node (ref "U$3") (pin "P17") (pinfunction "VCCINT_P17") (pintype "bidirectional"))
      (node (ref "U$3") (pin "P38") (pinfunction "VCCINT_P38") (pintype "bidirectional"))
      (node (ref "U$3") (pin "P66") (pinfunction "VCCINT_P66") (pintype "bidirectional"))
      (node (ref "U$3") (pin "P81") (pinfunction "VCCINT_P81") (pintype "bidirectional"))
      (node (ref "U9") (pin "2") (pinfunction "OUT_2") (pintype "output"))
      (node (ref "U9") (pin "4") (pinfunction "OUT_4") (pintype "output"))
    )
    (net (code "42") (name "VCC18") (class "Default")
      (node (ref "C10") (pin "1") (pinfunction "1_1") (pintype "passive"))
      (node (ref "C11") (pin "1") (pinfunction "1_1") (pintype "passive"))
      (node (ref "C14") (pin "1") (pinfunction "1_1") (pintype "passive"))
      (node (ref "IC2") (pin "12") (pinfunction "VCORE0_12") (pintype "bidirectional"))
      (node (ref "IC2") (pin "37") (pinfunction "VCORE1_37") (pintype "bidirectional"))
      (node (ref "IC2") (pin "49") (pinfunction "VREGOUT_49") (pintype "bidirectional"))
      (node (ref "IC2") (pin "64") (pinfunction "VCORE2_64") (pintype "bidirectional"))
    )
    (net (code "43") (name "VCC25") (class "Default")
      (node (ref "C18") (pin "1") (pinfunction "1_1") (pintype "passive"))
      (node (ref "C8") (pin "1") (pinfunction "1_1") (pintype "passive"))
      (node (ref "U$2") (pin "P$2") (pinfunction "VDD_P$2") (pintype "bidirectional"))
      (node (ref "U4") (pin "2") (pinfunction "OUT_2") (pintype "output"))
      (node (ref "U4") (pin "4") (pinfunction "OUT_4") (pintype "output"))
    )
    (net (code "44") (name "VCC33") (class "Default")
      (node (ref "3.3V") (pin "P$1") (pinfunction "P$1_P$1") (pintype "bidirectional"))
      (node (ref "C12") (pin "1") (pinfunction "1_1") (pintype "passive"))
      (node (ref "C13") (pin "1") (pinfunction "1_1") (pintype "passive"))
      (node (ref "C15") (pin "1") (pinfunction "1_1") (pintype "passive"))
      (node (ref "C16") (pin "1") (pinfunction "1_1") (pintype "passive"))
      (node (ref "C19") (pin "1") (pinfunction "1_1") (pintype "passive"))
      (node (ref "C2") (pin "1") (pinfunction "1_1") (pintype "passive"))
      (node (ref "C22") (pin "1") (pinfunction "1_1") (pintype "passive"))
      (node (ref "C27") (pin "1") (pinfunction "1_1") (pintype "passive"))
      (node (ref "C4") (pin "1") (pinfunction "1_1") (pintype "passive"))
      (node (ref "C5") (pin "1") (pinfunction "1_1") (pintype "passive"))
      (node (ref "C59") (pin "1") (pinfunction "1_1") (pintype "passive"))
      (node (ref "C60") (pin "1") (pinfunction "1_1") (pintype "passive"))
      (node (ref "C70") (pin "1") (pinfunction "1_1") (pintype "passive"))
      (node (ref "C72") (pin "1") (pinfunction "1_1") (pintype "passive"))
      (node (ref "C73") (pin "1") (pinfunction "1_1") (pintype "passive"))
      (node (ref "C74") (pin "1") (pinfunction "1_1") (pintype "passive"))
      (node (ref "C76") (pin "1") (pinfunction "1_1") (pintype "passive"))
      (node (ref "C78") (pin "1") (pinfunction "1_1") (pintype "passive"))
      (node (ref "C81") (pin "1") (pinfunction "1_1") (pintype "passive"))
      (node (ref "C9") (pin "1") (pinfunction "1_1") (pintype "passive"))
      (node (ref "IC2") (pin "20") (pinfunction "VCCIO0_20") (pintype "bidirectional"))
      (node (ref "IC2") (pin "31") (pinfunction "VCCIO1_31") (pintype "bidirectional"))
      (node (ref "IC2") (pin "42") (pinfunction "VCCIO2_42") (pintype "bidirectional"))
      (node (ref "IC2") (pin "50") (pinfunction "VREGIN_50") (pintype "bidirectional"))
      (node (ref "IC2") (pin "56") (pinfunction "VCCIO3_56") (pintype "bidirectional"))
      (node (ref "L3") (pin "2") (pinfunction "2_2") (pintype "passive"))
      (node (ref "L4") (pin "2") (pinfunction "2_2") (pintype "passive"))
      (node (ref "Q1") (pin "4") (pinfunction "VCC_4") (pintype "power_in"))
      (node (ref "Q2") (pin "4") (pinfunction "VCC_4") (pintype "power_in"))
      (node (ref "R2") (pin "2") (pinfunction "2_2") (pintype "passive"))
      (node (ref "R3") (pin "2") (pinfunction "2_2") (pintype "passive"))
      (node (ref "R4") (pin "2") (pinfunction "2_2") (pintype "passive"))
      (node (ref "R5") (pin "2") (pinfunction "2_2") (pintype "passive"))
      (node (ref "U$2") (pin "P$15") (pinfunction "OVDD_P$15") (pintype "bidirectional"))
      (node (ref "U$3") (pin "P11") (pinfunction "VCCO_3_P11") (pintype "bidirectional"))
      (node (ref "U$3") (pin "P22") (pinfunction "VCCAUX_P22") (pintype "bidirectional"))
      (node (ref "U$3") (pin "P26") (pinfunction "VCCO_2_P26") (pintype "bidirectional"))
      (node (ref "U$3") (pin "P45") (pinfunction "VCCO_2_P45") (pintype "bidirectional"))
      (node (ref "U$3") (pin "P55") (pinfunction "VCCAUX_P55") (pintype "bidirectional"))
      (node (ref "U$3") (pin "P67") (pinfunction "VCCO_1_P67") (pintype "bidirectional"))
      (node (ref "U$3") (pin "P79") (pinfunction "VCCO_0_P79") (pintype "bidirectional"))
      (node (ref "U$3") (pin "P92") (pinfunction "VCCAUX_P92") (pintype "bidirectional"))
      (node (ref "U$3") (pin "P96") (pinfunction "VCCO_0_P96") (pintype "bidirectional"))
      (node (ref "U2") (pin "5") (pinfunction "V+_5") (pintype "power_in"))
      (node (ref "U3") (pin "2") (pinfunction "OUT_2") (pintype "output"))
      (node (ref "U3") (pin "4") (pinfunction "OUT_4") (pintype "output"))
      (node (ref "U6") (pin "3") (pinfunction "ENABLE_3") (pintype "input"))
      (node (ref "U6") (pin "4") (pinfunction "VIN_4") (pintype "input"))
      (node (ref "U7") (pin "6") (pinfunction "ORG_6") (pintype "input"))
      (node (ref "U7") (pin "8") (pinfunction "VCC_8") (pintype "power_in"))
      (node (ref "U8") (pin "18") (pinfunction "VCCINT_18") (pintype "power_in"))
      (node (ref "U8") (pin "19") (pinfunction "VCCO_19") (pintype "power_in"))
      (node (ref "U8") (pin "20") (pinfunction "VCCJ_20") (pintype "power_in"))
    )
    (net (code "45") (name "unconnected-(IC2-ACBUS0{slash}TXDEN{slash}GPIOH0-Pad26)") (class "Default")
      (node (ref "IC2") (pin "26") (pinfunction "ACBUS0/TXDEN/GPIOH0_26") (pintype "bidirectional"))
    )
    (net (code "46") (name "unconnected-(IC2-ACBUS1{slash}GPIOH1-Pad27)") (class "Default")
      (node (ref "IC2") (pin "27") (pinfunction "ACBUS1/GPIOH1_27") (pintype "bidirectional"))
    )
    (net (code "47") (name "unconnected-(IC2-ACBUS2{slash}GPIOH2-Pad28)") (class "Default")
      (node (ref "IC2") (pin "28") (pinfunction "ACBUS2/GPIOH2_28") (pintype "bidirectional"))
    )
    (net (code "48") (name "unconnected-(IC2-ACBUS3{slash}RXLED#{slash}GPIOH3-Pad29)") (class "Default")
      (node (ref "IC2") (pin "29") (pinfunction "ACBUS3/RXLED#/GPIOH3_29") (pintype "bidirectional"))
    )
    (net (code "49") (name "unconnected-(IC2-ACBUS4{slash}TXLED#{slash}GPIOH4-Pad30)") (class "Default")
      (node (ref "IC2") (pin "30") (pinfunction "ACBUS4/TXLED#/GPIOH4_30") (pintype "bidirectional"))
    )
    (net (code "50") (name "unconnected-(IC2-ACBUS5{slash}GPIOH5-Pad32)") (class "Default")
      (node (ref "IC2") (pin "32") (pinfunction "ACBUS5/GPIOH5_32") (pintype "bidirectional"))
    )
    (net (code "51") (name "unconnected-(IC2-ACBUS6{slash}GPIOH6-Pad33)") (class "Default")
      (node (ref "IC2") (pin "33") (pinfunction "ACBUS6/GPIOH6_33") (pintype "bidirectional"))
    )
    (net (code "52") (name "unconnected-(IC2-ACBUS7{slash}GPIOH7-Pad34)") (class "Default")
      (node (ref "IC2") (pin "34") (pinfunction "ACBUS7/GPIOH7_34") (pintype "bidirectional"))
    )
    (net (code "53") (name "unconnected-(IC2-ADBUS0{slash}TXD{slash}TCK{slash}SK-Pad16)") (class "Default")
      (node (ref "IC2") (pin "16") (pinfunction "ADBUS0/TXD/TCK/SK_16") (pintype "bidirectional"))
    )
    (net (code "54") (name "unconnected-(IC2-ADBUS1{slash}RXD{slash}TDI{slash}DO-Pad17)") (class "Default")
      (node (ref "IC2") (pin "17") (pinfunction "ADBUS1/RXD/TDI/DO_17") (pintype "bidirectional"))
    )
    (net (code "55") (name "unconnected-(IC2-ADBUS2{slash}RTS#{slash}TDO{slash}DI-Pad18)") (class "Default")
      (node (ref "IC2") (pin "18") (pinfunction "ADBUS2/RTS#/TDO/DI_18") (pintype "bidirectional"))
    )
    (net (code "56") (name "unconnected-(IC2-ADBUS3{slash}CTS#{slash}TMS{slash}CS-Pad19)") (class "Default")
      (node (ref "IC2") (pin "19") (pinfunction "ADBUS3/CTS#/TMS/CS_19") (pintype "bidirectional"))
    )
    (net (code "57") (name "unconnected-(IC2-ADBUS4{slash}DTR#{slash}GPIOL0-Pad21)") (class "Default")
      (node (ref "IC2") (pin "21") (pinfunction "ADBUS4/DTR#/GPIOL0_21") (pintype "bidirectional"))
    )
    (net (code "58") (name "unconnected-(IC2-ADBUS5{slash}DSR#{slash}GPIOL1-Pad22)") (class "Default")
      (node (ref "IC2") (pin "22") (pinfunction "ADBUS5/DSR#/GPIOL1_22") (pintype "bidirectional"))
    )
    (net (code "59") (name "unconnected-(IC2-ADBUS6{slash}DCD#{slash}GPIOL2-Pad23)") (class "Default")
      (node (ref "IC2") (pin "23") (pinfunction "ADBUS6/DCD#/GPIOL2_23") (pintype "bidirectional"))
    )
    (net (code "60") (name "unconnected-(IC2-ADBUS7{slash}RI#{slash}GPIOL3-Pad24)") (class "Default")
      (node (ref "IC2") (pin "24") (pinfunction "ADBUS7/RI#/GPIOL3_24") (pintype "bidirectional"))
    )
    (net (code "61") (name "unconnected-(IC2-BCBUS0{slash}GPIOH1-Pad48)") (class "Default")
      (node (ref "IC2") (pin "48") (pinfunction "BCBUS0/GPIOH1_48") (pintype "bidirectional"))
    )
    (net (code "62") (name "unconnected-(IC2-BCBUS1{slash}GPIOH2-Pad52)") (class "Default")
      (node (ref "IC2") (pin "52") (pinfunction "BCBUS1/GPIOH2_52") (pintype "bidirectional"))
    )
    (net (code "63") (name "unconnected-(IC2-BCBUS2-Pad53)") (class "Default")
      (node (ref "IC2") (pin "53") (pinfunction "BCBUS2_53") (pintype "bidirectional"))
    )
    (net (code "64") (name "unconnected-(IC2-BCBUS3{slash}RXLED#{slash}GPIOH3-Pad54)") (class "Default")
      (node (ref "IC2") (pin "54") (pinfunction "BCBUS3/RXLED#/GPIOH3_54") (pintype "bidirectional"))
    )
    (net (code "65") (name "unconnected-(IC2-BCBUS4{slash}TXLED#{slash}GPIOH4-Pad55)") (class "Default")
      (node (ref "IC2") (pin "55") (pinfunction "BCBUS4/TXLED#/GPIOH4_55") (pintype "bidirectional"))
    )
    (net (code "66") (name "unconnected-(IC2-BCBUS5{slash}GPIOH5-Pad57)") (class "Default")
      (node (ref "IC2") (pin "57") (pinfunction "BCBUS5/GPIOH5_57") (pintype "bidirectional"))
    )
    (net (code "67") (name "unconnected-(IC2-BCBUS6{slash}GPIOH6-Pad58)") (class "Default")
      (node (ref "IC2") (pin "58") (pinfunction "BCBUS6/GPIOH6_58") (pintype "bidirectional"))
    )
    (net (code "68") (name "unconnected-(IC2-BCBUS7{slash}GPIOH7-Pad59)") (class "Default")
      (node (ref "IC2") (pin "59") (pinfunction "BCBUS7/GPIOH7_59") (pintype "bidirectional"))
    )
    (net (code "69") (name "unconnected-(IC2-BDBUS4{slash}DTR#{slash}GPIOL0-Pad43)") (class "Default")
      (node (ref "IC2") (pin "43") (pinfunction "BDBUS4/DTR#/GPIOL0_43") (pintype "bidirectional"))
    )
    (net (code "70") (name "unconnected-(IC2-BDBUS5{slash}DSR#{slash}GPIOL1-Pad44)") (class "Default")
      (node (ref "IC2") (pin "44") (pinfunction "BDBUS5/DSR#/GPIOL1_44") (pintype "bidirectional"))
    )
    (net (code "71") (name "unconnected-(IC2-BDBUS6{slash}DCD#{slash}GPIOL2-Pad45)") (class "Default")
      (node (ref "IC2") (pin "45") (pinfunction "BDBUS6/DCD#/GPIOL2_45") (pintype "bidirectional"))
    )
    (net (code "72") (name "unconnected-(IC2-BDBUS7{slash}RI#{slash}GPIOL3-Pad46)") (class "Default")
      (node (ref "IC2") (pin "46") (pinfunction "BDBUS7/RI#/GPIOL3_46") (pintype "bidirectional"))
    )
    (net (code "73") (name "unconnected-(IC2-OSC0-Pad3)") (class "Default")
      (node (ref "IC2") (pin "3") (pinfunction "OSC0_3") (pintype "bidirectional"))
    )
    (net (code "74") (name "unconnected-(IC2-PWREN#-Pad60)") (class "Default")
      (node (ref "IC2") (pin "60") (pinfunction "PWREN#_60") (pintype "bidirectional"))
    )
    (net (code "75") (name "unconnected-(IC2-SUSPEND#-Pad36)") (class "Default")
      (node (ref "IC2") (pin "36") (pinfunction "SUSPEND#_36") (pintype "bidirectional"))
    )
    (net (code "76") (name "unconnected-(Q1-OE-Pad1)") (class "Default")
      (node (ref "Q1") (pin "1") (pinfunction "OE_1") (pintype "input"))
    )
    (net (code "77") (name "unconnected-(Q2-OE-Pad1)") (class "Default")
      (node (ref "Q2") (pin "1") (pinfunction "OE_1") (pintype "input"))
    )
    (net (code "78") (name "unconnected-(U$3A-IO_L01N_0-PadP78)") (class "Default")
      (node (ref "U$3") (pin "P78") (pinfunction "IO_L01N_0_P78") (pintype "bidirectional"))
    )
    (net (code "79") (name "unconnected-(U$3A-IO_L01P_0{slash}VREF_0-PadP77)") (class "Default")
      (node (ref "U$3") (pin "P77") (pinfunction "IO_L01P_0/VREF_0_P77") (pintype "bidirectional"))
    )
    (net (code "80") (name "unconnected-(U$3A-IO_L02N_0{slash}GCLK5-PadP84)") (class "Default")
      (node (ref "U$3") (pin "P84") (pinfunction "IO_L02N_0/GCLK5_P84") (pintype "bidirectional"))
    )
    (net (code "81") (name "unconnected-(U$3A-IO_L03P_0{slash}GCLK6-PadP85)") (class "Default")
      (node (ref "U$3") (pin "P85") (pinfunction "IO_L03P_0/GCLK6_P85") (pintype "bidirectional"))
    )
    (net (code "82") (name "unconnected-(U$3A-IO_L05N_0-PadP94)") (class "Default")
      (node (ref "U$3") (pin "P94") (pinfunction "IO_L05N_0_P94") (pintype "bidirectional"))
    )
    (net (code "83") (name "unconnected-(U$3A-IO_L05P_0-PadP93)") (class "Default")
      (node (ref "U$3") (pin "P93") (pinfunction "IO_L05P_0_P93") (pintype "bidirectional"))
    )
    (net (code "84") (name "unconnected-(U$3A-IO_L06P_0{slash}VREF_0-PadP98)") (class "Default")
      (node (ref "U$3") (pin "P98") (pinfunction "IO_L06P_0/VREF_0_P98") (pintype "bidirectional"))
    )
    (net (code "85") (name "unconnected-(U$3A-IP_0-PadP97)") (class "Default")
      (node (ref "U$3") (pin "P97") (pinfunction "IP_0_P97") (pintype "bidirectional"))
    )
    (net (code "86") (name "unconnected-(U$3A-IP_0{slash}VREF_0-PadP82)") (class "Default")
      (node (ref "U$3") (pin "P82") (pinfunction "IP_0/VREF_0_P82") (pintype "bidirectional"))
    )
    (net (code "87") (name "unconnected-(U$3B-IO_L01N_1-PadP57)") (class "Default")
      (node (ref "U$3") (pin "P57") (pinfunction "IO_L01N_1_P57") (pintype "bidirectional"))
    )
    (net (code "88") (name "unconnected-(U$3B-IO_L01P_1-PadP56)") (class "Default")
      (node (ref "U$3") (pin "P56") (pinfunction "IO_L01P_1_P56") (pintype "bidirectional"))
    )
    (net (code "89") (name "unconnected-(U$3B-IO_L02N_1{slash}RHCLK1-PadP60)") (class "Default")
      (node (ref "U$3") (pin "P60") (pinfunction "IO_L02N_1/RHCLK1_P60") (pintype "bidirectional"))
    )
    (net (code "90") (name "unconnected-(U$3B-IO_L02P_1{slash}RHCLK0-PadP59)") (class "Default")
      (node (ref "U$3") (pin "P59") (pinfunction "IO_L02P_1/RHCLK0_P59") (pintype "bidirectional"))
    )
    (net (code "91") (name "unconnected-(U$3B-IO_L03N_1{slash}TRDY1{slash}RHCLK3-PadP62)") (class "Default")
      (node (ref "U$3") (pin "P62") (pinfunction "IO_L03N_1/TRDY1/RHCLK3_P62") (pintype "bidirectional"))
    )
    (net (code "92") (name "unconnected-(U$3B-IO_L03P_1{slash}RHCLK2-PadP61)") (class "Default")
      (node (ref "U$3") (pin "P61") (pinfunction "IO_L03P_1/RHCLK2_P61") (pintype "bidirectional"))
    )
    (net (code "93") (name "unconnected-(U$3B-IO_L04N_1{slash}RHCLK7-PadP65)") (class "Default")
      (node (ref "U$3") (pin "P65") (pinfunction "IO_L04N_1/RHCLK7_P65") (pintype "bidirectional"))
    )
    (net (code "94") (name "unconnected-(U$3B-IO_L04P_1{slash}IRDY1{slash}RHCLK6-PadP64)") (class "Default")
      (node (ref "U$3") (pin "P64") (pinfunction "IO_L04P_1/IRDY1/RHCLK6_P64") (pintype "bidirectional"))
    )
    (net (code "95") (name "unconnected-(U$3B-IO_L05N_1-PadP71)") (class "Default")
      (node (ref "U$3") (pin "P71") (pinfunction "IO_L05N_1_P71") (pintype "bidirectional"))
    )
    (net (code "96") (name "unconnected-(U$3B-IO_L05P_1-PadP70)") (class "Default")
      (node (ref "U$3") (pin "P70") (pinfunction "IO_L05P_1_P70") (pintype "bidirectional"))
    )
    (net (code "97") (name "unconnected-(U$3B-IO_L06N_1-PadP73)") (class "Default")
      (node (ref "U$3") (pin "P73") (pinfunction "IO_L06N_1_P73") (pintype "bidirectional"))
    )
    (net (code "98") (name "unconnected-(U$3B-IO_L06P_1-PadP72)") (class "Default")
      (node (ref "U$3") (pin "P72") (pinfunction "IO_L06P_1_P72") (pintype "bidirectional"))
    )
    (net (code "99") (name "unconnected-(U$3B-IP_1{slash}VREF_1-PadP68)") (class "Default")
      (node (ref "U$3") (pin "P68") (pinfunction "IP_1/VREF_1_P68") (pintype "bidirectional"))
    )
    (net (code "100") (name "unconnected-(U$3C-IO_2{slash}MOSI{slash}CSI_B-PadP46)") (class "Default")
      (node (ref "U$3") (pin "P46") (pinfunction "IO_2/MOSI/CSI_B_P46") (pintype "bidirectional"))
    )
    (net (code "101") (name "unconnected-(U$3C-IO_L02N_2{slash}CSO_B-PadP27)") (class "Default")
      (node (ref "U$3") (pin "P27") (pinfunction "IO_L02N_2/CSO_B_P27") (pintype "bidirectional"))
    )
    (net (code "102") (name "unconnected-(U$3C-IO_L03N_2{slash}VS2-PadP29)") (class "Default")
      (node (ref "U$3") (pin "P29") (pinfunction "IO_L03N_2/VS2_P29") (pintype "bidirectional"))
    )
    (net (code "103") (name "unconnected-(U$3C-IO_L03P_2{slash}RDWR_B-PadP28)") (class "Default")
      (node (ref "U$3") (pin "P28") (pinfunction "IO_L03P_2/RDWR_B_P28") (pintype "bidirectional"))
    )
    (net (code "104") (name "unconnected-(U$3C-IO_L04N_2{slash}VS0-PadP31)") (class "Default")
      (node (ref "U$3") (pin "P31") (pinfunction "IO_L04N_2/VS0_P31") (pintype "bidirectional"))
    )
    (net (code "105") (name "unconnected-(U$3C-IO_L04P_2{slash}VS1-PadP30)") (class "Default")
      (node (ref "U$3") (pin "P30") (pinfunction "IO_L04P_2/VS1_P30") (pintype "bidirectional"))
    )
    (net (code "106") (name "unconnected-(U$3C-IO_L05N_2-PadP33)") (class "Default")
      (node (ref "U$3") (pin "P33") (pinfunction "IO_L05N_2_P33") (pintype "bidirectional"))
    )
    (net (code "107") (name "unconnected-(U$3C-IO_L05P_2-PadP32)") (class "Default")
      (node (ref "U$3") (pin "P32") (pinfunction "IO_L05P_2_P32") (pintype "bidirectional"))
    )
    (net (code "108") (name "unconnected-(U$3C-IO_L06N_2{slash}D6-PadP35)") (class "Default")
      (node (ref "U$3") (pin "P35") (pinfunction "IO_L06N_2/D6_P35") (pintype "bidirectional"))
    )
    (net (code "109") (name "unconnected-(U$3C-IO_L06P_2{slash}D7-PadP34)") (class "Default")
      (node (ref "U$3") (pin "P34") (pinfunction "IO_L06P_2/D7_P34") (pintype "bidirectional"))
    )
    (net (code "110") (name "unconnected-(U$3C-IO_L07P_2{slash}D5-PadP36)") (class "Default")
      (node (ref "U$3") (pin "P36") (pinfunction "IO_L07P_2/D5_P36") (pintype "bidirectional"))
    )
    (net (code "111") (name "unconnected-(U$3C-IO_L07_2{slash}D4-PadP37)") (class "Default")
      (node (ref "U$3") (pin "P37") (pinfunction "IO_L07_2/D4_P37") (pintype "bidirectional"))
    )
    (net (code "112") (name "unconnected-(U$3C-IO_L08N_2{slash}GCLK15-PadP41)") (class "Default")
      (node (ref "U$3") (pin "P41") (pinfunction "IO_L08N_2/GCLK15_P41") (pintype "bidirectional"))
    )
    (net (code "113") (name "unconnected-(U$3C-IO_L08P_2{slash}GCLK14-PadP40)") (class "Default")
      (node (ref "U$3") (pin "P40") (pinfunction "IO_L08P_2/GCLK14_P40") (pintype "bidirectional"))
    )
    (net (code "114") (name "unconnected-(U$3C-IO_L09N_2{slash}GCLK1-PadP44)") (class "Default")
      (node (ref "U$3") (pin "P44") (pinfunction "IO_L09N_2/GCLK1_P44") (pintype "bidirectional"))
    )
    (net (code "115") (name "unconnected-(U$3C-IO_L09P_2{slash}GCLK0-PadP43)") (class "Default")
      (node (ref "U$3") (pin "P43") (pinfunction "IO_L09P_2/GCLK0_P43") (pintype "bidirectional"))
    )
    (net (code "116") (name "unconnected-(U$3C-IO_L10N_2{slash}D3-PadP49)") (class "Default")
      (node (ref "U$3") (pin "P49") (pinfunction "IO_L10N_2/D3_P49") (pintype "bidirectional"))
    )
    (net (code "117") (name "unconnected-(U$3C-IO_L11N_2{slash}D1-PadP52)") (class "Default")
      (node (ref "U$3") (pin "P52") (pinfunction "IO_L11N_2/D1_P52") (pintype "bidirectional"))
    )
    (net (code "118") (name "unconnected-(U$3C-IO_L11P_2{slash}D2-PadP50)") (class "Default")
      (node (ref "U$3") (pin "P50") (pinfunction "IO_L11P_2/D2_P50") (pintype "bidirectional"))
    )
    (net (code "119") (name "unconnected-(U$3C-IP_2{slash}VREF_2-PadP39)") (class "Default")
      (node (ref "U$3") (pin "P39") (pinfunction "IP_2/VREF_2_P39") (pintype "bidirectional"))
    )
    (net (code "120") (name "unconnected-(U$3D-IO_L03N_3{slash}LHCLK1-PadP10)") (class "Default")
      (node (ref "U$3") (pin "P10") (pinfunction "IO_L03N_3/LHCLK1_P10") (pintype "bidirectional"))
    )
    (net (code "121") (name "unconnected-(U$3D-IO_L03P_3{slash}LHCLK0-PadP9)") (class "Default")
      (node (ref "U$3") (pin "P9") (pinfunction "IO_L03P_3/LHCLK0_P9") (pintype "bidirectional"))
    )
    (net (code "122") (name "unconnected-(U$3D-IO_L04P_3{slash}LHCLK2-PadP12)") (class "Default")
      (node (ref "U$3") (pin "P12") (pinfunction "IO_L04P_3/LHCLK2_P12") (pintype "bidirectional"))
    )
    (net (code "123") (name "unconnected-(U$3D-IO_L06N_3-PadP20)") (class "Default")
      (node (ref "U$3") (pin "P20") (pinfunction "IO_L06N_3_P20") (pintype "bidirectional"))
    )
    (net (code "124") (name "unconnected-(U$3D-IO_L06P_3-PadP19)") (class "Default")
      (node (ref "U$3") (pin "P19") (pinfunction "IO_L06P_3_P19") (pintype "bidirectional"))
    )
    (net (code "125") (name "unconnected-(U$3D-IP_3-PadP21)") (class "Default")
      (node (ref "U$3") (pin "P21") (pinfunction "IP_3_P21") (pintype "bidirectional"))
    )
    (net (code "126") (name "unconnected-(U$3D-IP_3{slash}VREF_3-PadP7)") (class "Default")
      (node (ref "U$3") (pin "P7") (pinfunction "IP_3/VREF_3_P7") (pintype "bidirectional"))
    )
    (net (code "127") (name "unconnected-(U8-(DNC)-Pad16)") (class "Default")
      (node (ref "U8") (pin "16") (pinfunction "(DNC)_16") (pintype "no_connect"))
    )
    (net (code "128") (name "unconnected-(U8-(DNC)_2-Pad12)") (class "Default")
      (node (ref "U8") (pin "12") (pinfunction "(DNC)_2_12") (pintype "no_connect"))
    )
    (net (code "129") (name "unconnected-(U8-(DNC)_3-Pad2)") (class "Default")
      (node (ref "U8") (pin "2") (pinfunction "(DNC)_3_2") (pintype "no_connect"))
    )
    (net (code "130") (name "unconnected-(U8-(DNC)_4-Pad15)") (class "Default")
      (node (ref "U8") (pin "15") (pinfunction "(DNC)_4_15") (pintype "no_connect"))
    )
    (net (code "131") (name "unconnected-(U8-(DNC)_5-Pad9)") (class "Default")
      (node (ref "U8") (pin "9") (pinfunction "(DNC)_5_9") (pintype "no_connect"))
    )
    (net (code "132") (name "unconnected-(U8-(DNC)_6-Pad14)") (class "Default")
      (node (ref "U8") (pin "14") (pinfunction "(DNC)_6_14") (pintype "no_connect"))
    )
    (net (code "133") (name "unconnected-(U8-~{CEO}-Pad13)") (class "Default")
      (node (ref "U8") (pin "13") (pinfunction "~{CEO}_13") (pintype "output"))
    )
  )
)
